# SparkFun_Window_Comparator.net
KiCad netlist of a schematic drawn in EAGLE
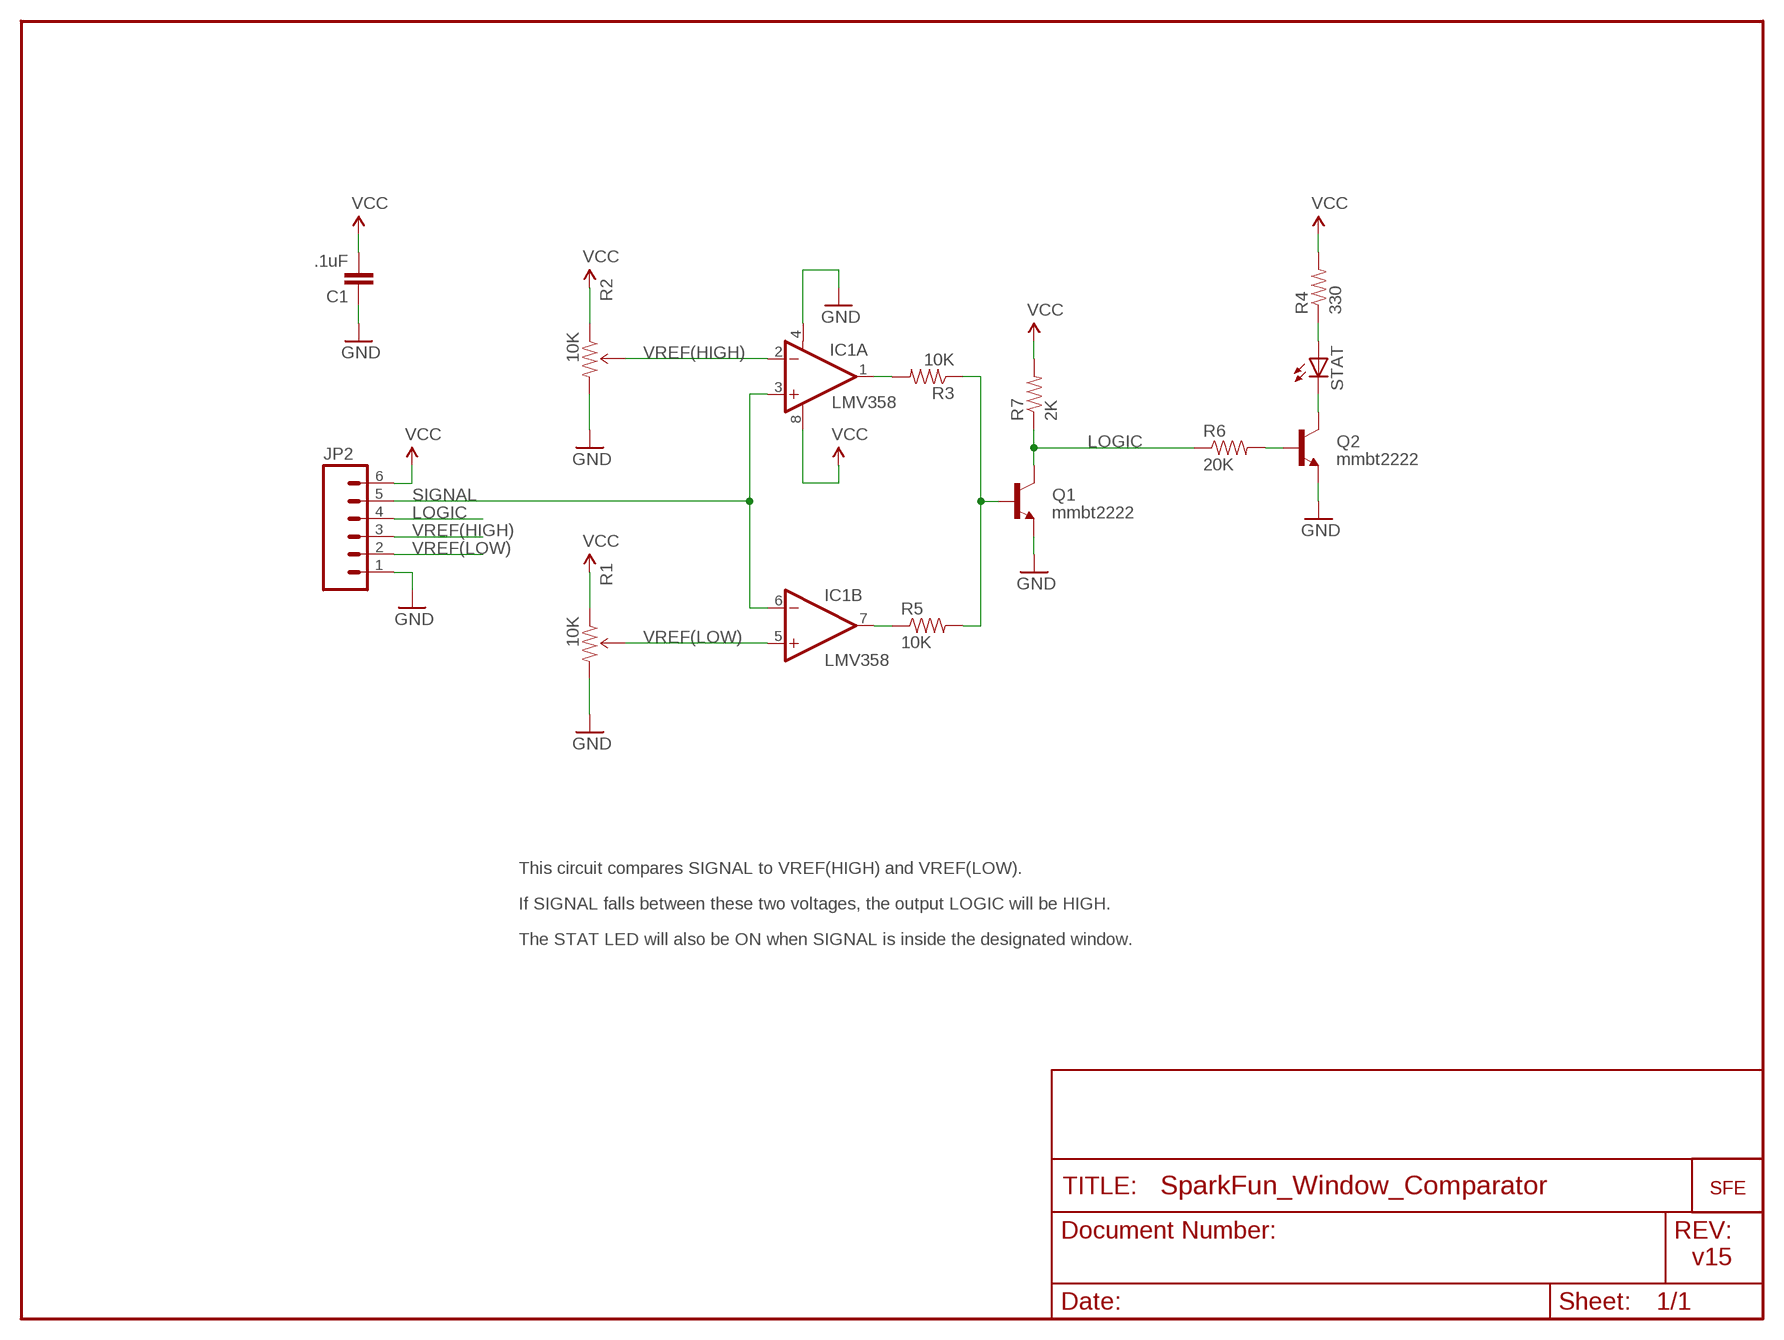
[diagram p0: schematic, sheet 1]

(export (version "E")
  (design (tool "Eeschema 10.0.6"))
  (components
    (comp (ref "C1")
      (value ".1uF")
      (footprint "eagle-import:0603-CAP")
      (libsource (lib "eagle-import") (part "CAP0603-CAP"))
    )
    (comp (ref "IC1")
      (value "LMV358")
      (footprint "eagle-import:SO08")
      (libsource (lib "eagle-import") (part "OPAMP-DUALU"))
    )
    (comp (ref "JP2")
      (value "M06SIP")
      (footprint "eagle-import:1X06")
      (libsource (lib "eagle-import") (part "M06SIP"))
    )
    (comp (ref "Q1")
      (value "mmbt2222")
      (footprint "eagle-import:SOT23-3")
      (libsource (lib "eagle-import") (part "TRANSISTOR_NPNSOT23-3"))
    )
    (comp (ref "Q2")
      (value "mmbt2222")
      (footprint "eagle-import:SOT23-3")
      (libsource (lib "eagle-import") (part "TRANSISTOR_NPNSOT23-3"))
    )
    (comp (ref "R1")
      (value "10K")
      (footprint "eagle-import:TRIMPOT-3MM")
      (libsource (lib "eagle-import") (part "TRIMPOTSMD"))
    )
    (comp (ref "R2")
      (value "10K")
      (footprint "eagle-import:TRIMPOT-3MM")
      (libsource (lib "eagle-import") (part "TRIMPOTSMD"))
    )
    (comp (ref "R3")
      (value "10K")
      (footprint "eagle-import:0603-RES")
      (libsource (lib "eagle-import") (part "RESISTOR0603-RES"))
    )
    (comp (ref "R4")
      (value "330")
      (footprint "eagle-import:0603-RES")
      (libsource (lib "eagle-import") (part "RESISTOR0603-RES"))
    )
    (comp (ref "R5")
      (value "10K")
      (footprint "eagle-import:0603-RES")
      (libsource (lib "eagle-import") (part "RESISTOR0603-RES"))
    )
    (comp (ref "R6")
      (value "20K")
      (footprint "eagle-import:0603-RES")
      (libsource (lib "eagle-import") (part "RESISTOR0603-RES"))
    )
    (comp (ref "R7")
      (value "2K")
      (footprint "eagle-import:0603-RES")
      (libsource (lib "eagle-import") (part "RESISTOR0603-RES"))
    )
    (comp (ref "STAT")
      (value "LED0603")
      (footprint "eagle-import:LED-0603")
      (libsource (lib "eagle-import") (part "LED0603"))
    )
    (comp (ref "U$3")
      (value "LOGO-SFENEW")
      (footprint "eagle-import:SFE-NEW-WEBLOGO")
      (libsource (lib "eagle-import") (part "LOGO-SFENEW"))
    )
  )
  (nets
    (net (code "1") (name "/LOGIC") (class "Default")
      (node (ref "JP2") (pin "4") (pinfunction "4_4") (pintype "passive"))
      (node (ref "Q1") (pin "3") (pinfunction "C_3") (pintype "passive"))
      (node (ref "R6") (pin "1") (pinfunction "1_1") (pintype "passive"))
      (node (ref "R7") (pin "1") (pinfunction "1_1") (pintype "passive"))
    )
    (net (code "2") (name "/SIGNAL") (class "Default")
      (node (ref "IC1") (pin "3") (pinfunction "+IN_3") (pintype "input"))
      (node (ref "IC1") (pin "6") (pinfunction "-IN_6") (pintype "input"))
      (node (ref "JP2") (pin "5") (pinfunction "5_5") (pintype "passive"))
    )
    (net (code "3") (name "/VREF(HIGH)") (class "Default")
      (node (ref "IC1") (pin "2") (pinfunction "-IN_2") (pintype "input"))
      (node (ref "JP2") (pin "3") (pinfunction "3_3") (pintype "passive"))
      (node (ref "R2") (pin "2") (pinfunction "WIPER_2") (pintype "passive"))
    )
    (net (code "4") (name "/VREF(LOW)") (class "Default")
      (node (ref "IC1") (pin "5") (pinfunction "+IN_5") (pintype "input"))
      (node (ref "JP2") (pin "2") (pinfunction "2_2") (pintype "passive"))
      (node (ref "R1") (pin "2") (pinfunction "WIPER_2") (pintype "passive"))
    )
    (net (code "5") (name "GND") (class "Default")
      (node (ref "C1") (pin "1") (pinfunction "1_1") (pintype "passive"))
      (node (ref "IC1") (pin "4") (pinfunction "V-_4") (pintype "power_in"))
      (node (ref "JP2") (pin "1") (pinfunction "1_1") (pintype "passive"))
      (node (ref "Q1") (pin "2") (pinfunction "E_2") (pintype "passive"))
      (node (ref "Q2") (pin "2") (pinfunction "E_2") (pintype "passive"))
      (node (ref "R1") (pin "3") (pinfunction "CW_3") (pintype "passive"))
      (node (ref "R2") (pin "3") (pinfunction "CW_3") (pintype "passive"))
    )
    (net (code "6") (name "Net-(IC1A-OUT)") (class "Default")
      (node (ref "IC1") (pin "1") (pinfunction "OUT_1") (pintype "output"))
      (node (ref "R3") (pin "2") (pinfunction "2_2") (pintype "passive"))
    )
    (net (code "7") (name "Net-(IC1B-OUT)") (class "Default")
      (node (ref "IC1") (pin "7") (pinfunction "OUT_7") (pintype "output"))
      (node (ref "R5") (pin "1") (pinfunction "1_1") (pintype "passive"))
    )
    (net (code "8") (name "Net-(Q1-B)") (class "Default")
      (node (ref "Q1") (pin "1") (pinfunction "B_1") (pintype "passive"))
      (node (ref "R3") (pin "1") (pinfunction "1_1") (pintype "passive"))
      (node (ref "R5") (pin "2") (pinfunction "2_2") (pintype "passive"))
    )
    (net (code "9") (name "Net-(Q2-B)") (class "Default")
      (node (ref "Q2") (pin "1") (pinfunction "B_1") (pintype "passive"))
      (node (ref "R6") (pin "2") (pinfunction "2_2") (pintype "passive"))
    )
    (net (code "10") (name "Net-(Q2-C)") (class "Default")
      (node (ref "Q2") (pin "3") (pinfunction "C_3") (pintype "passive"))
      (node (ref "STAT") (pin "C") (pinfunction "C_C") (pintype "passive"))
    )
    (net (code "11") (name "Net-(R4-Pad1)") (class "Default")
      (node (ref "R4") (pin "1") (pinfunction "1_1") (pintype "passive"))
      (node (ref "STAT") (pin "A") (pinfunction "A_A") (pintype "passive"))
    )
    (net (code "12") (name "VCC") (class "Default")
      (node (ref "C1") (pin "2") (pinfunction "2_2") (pintype "passive"))
      (node (ref "IC1") (pin "8") (pinfunction "V+_8") (pintype "power_in"))
      (node (ref "JP2") (pin "6") (pinfunction "6_6") (pintype "passive"))
      (node (ref "R1") (pin "1") (pinfunction "CCW_1") (pintype "passive"))
      (node (ref "R2") (pin "1") (pinfunction "CCW_1") (pintype "passive"))
      (node (ref "R4") (pin "2") (pinfunction "2_2") (pintype "passive"))
      (node (ref "R7") (pin "2") (pinfunction "2_2") (pintype "passive"))
    )
  )
)
